# Mabee_Relay_10A_V1_1.net
KiCad netlist of a schematic drawn in EAGLE
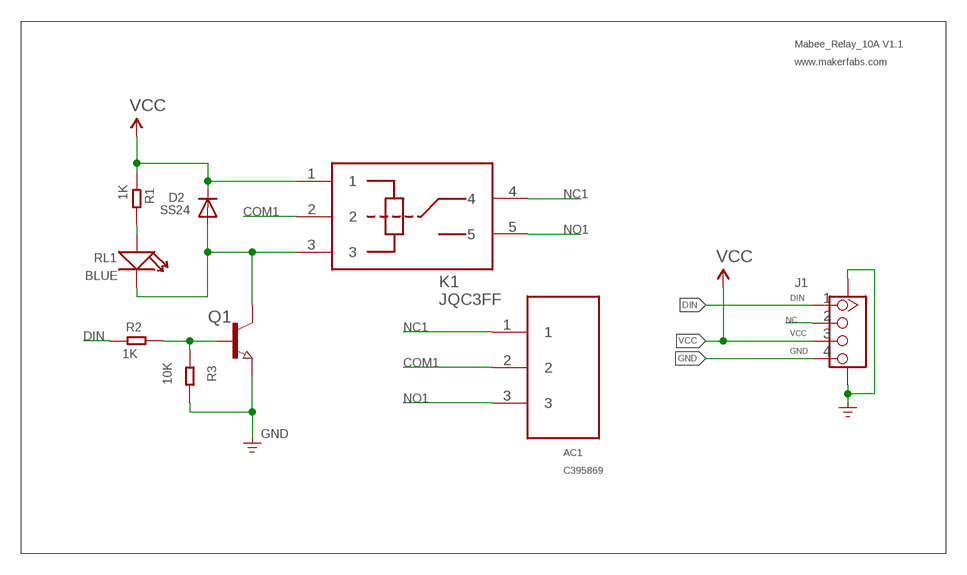
[diagram p0: schematic, sheet 1]

(export (version "E")
  (design (tool "Eeschema 10.0.6"))
  (components
    (comp (ref "AC1")
      (value "C395869")
      (footprint "eagle-import:PIN_3P")
      (libsource (lib "eagle-import") (part "C395869"))
    )
    (comp (ref "D2")
      (value "SS24")
      (footprint "eagle-import:SMADIODE")
      (libsource (lib "eagle-import") (part "DIODESMA"))
    )
    (comp (ref "J1")
      (value "GROVE-CONNECTOR-SMD'90D'")
      (footprint "eagle-import:HW4-SMD-2.0-90D")
      (libsource (lib "eagle-import") (part "GROVE-CONNECTOR-SMD'90D'"))
    )
    (comp (ref "K1")
      (value "JQC3FF")
      (footprint "eagle-import:DIP5_JQC3FF")
      (libsource (lib "eagle-import") (part "JQC3FF"))
    )
    (comp (ref "Q1")
      (value "NPN-TRANSISTOR_SOT23")
      (footprint "eagle-import:SOT23")
      (libsource (lib "eagle-import") (part "NPN-TRANSISTOR_SOT23"))
    )
    (comp (ref "R1")
      (value "1K")
      (footprint "eagle-import:R0603")
      (libsource (lib "eagle-import") (part "R-0603"))
    )
    (comp (ref "R2")
      (value "1K")
      (footprint "eagle-import:R0603")
      (libsource (lib "eagle-import") (part "R-0603"))
    )
    (comp (ref "R3")
      (value "10K")
      (footprint "eagle-import:R0603")
      (libsource (lib "eagle-import") (part "R-0603"))
    )
    (comp (ref "RL1")
      (value "BLUE")
      (footprint "eagle-import:LED-0603")
      (libsource (lib "eagle-import") (part "LED'0603'"))
    )
  )
  (nets
    (net (code "1") (name "/COM1") (class "Default")
      (node (ref "AC1") (pin "2") (pinfunction "2_2") (pintype "bidirectional"))
      (node (ref "K1") (pin "2") (pinfunction "2_2") (pintype "bidirectional"))
    )
    (net (code "2") (name "/NC") (class "Default")
      (node (ref "J1") (pin "2") (pinfunction "2_2") (pintype "bidirectional"))
    )
    (net (code "3") (name "/NC1") (class "Default")
      (node (ref "AC1") (pin "1") (pinfunction "1_1") (pintype "bidirectional"))
      (node (ref "K1") (pin "4") (pinfunction "4_4") (pintype "bidirectional"))
    )
    (net (code "4") (name "/NO1") (class "Default")
      (node (ref "AC1") (pin "3") (pinfunction "3_3") (pintype "bidirectional"))
      (node (ref "K1") (pin "5") (pinfunction "5_5") (pintype "bidirectional"))
    )
    (net (code "5") (name "DIN") (class "Default")
      (node (ref "J1") (pin "1") (pinfunction "1_1") (pintype "bidirectional"))
      (node (ref "R2") (pin "1") (pinfunction "1_1") (pintype "passive"))
    )
    (net (code "6") (name "GND") (class "Default")
      (node (ref "J1") (pin "4") (pinfunction "4_4") (pintype "bidirectional"))
      (node (ref "J1") (pin "SS1") (pinfunction "SS1_SS1") (pintype "bidirectional"))
      (node (ref "J1") (pin "SS2") (pinfunction "SS2_SS2") (pintype "bidirectional"))
      (node (ref "Q1") (pin "2") (pinfunction "E_2") (pintype "passive"))
      (node (ref "R3") (pin "2") (pinfunction "2_2") (pintype "passive"))
    )
    (net (code "7") (name "Net-(Q1-B)") (class "Default")
      (node (ref "Q1") (pin "1") (pinfunction "B_1") (pintype "passive"))
      (node (ref "R2") (pin "2") (pinfunction "2_2") (pintype "passive"))
      (node (ref "R3") (pin "1") (pinfunction "1_1") (pintype "passive"))
    )
    (net (code "8") (name "Net-(Q1-C)") (class "Default")
      (node (ref "D2") (pin "A") (pinfunction "A_A") (pintype "passive"))
      (node (ref "K1") (pin "3") (pinfunction "3_3") (pintype "bidirectional"))
      (node (ref "Q1") (pin "3") (pinfunction "C_3") (pintype "passive"))
      (node (ref "RL1") (pin "-") (pinfunction "-_-") (pintype "passive"))
    )
    (net (code "9") (name "Net-(R1-Pad2)") (class "Default")
      (node (ref "R1") (pin "2") (pinfunction "2_2") (pintype "passive"))
      (node (ref "RL1") (pin "+") (pinfunction "+_+") (pintype "passive"))
    )
    (net (code "10") (name "VCC") (class "Default")
      (node (ref "D2") (pin "C") (pinfunction "C_C") (pintype "passive"))
      (node (ref "J1") (pin "3") (pinfunction "3_3") (pintype "bidirectional"))
      (node (ref "K1") (pin "1") (pinfunction "1_1") (pintype "bidirectional"))
      (node (ref "R1") (pin "1") (pinfunction "1_1") (pintype "passive"))
    )
  )
)
